# SHT4x.net
KiCad netlist of a schematic drawn in EAGLE
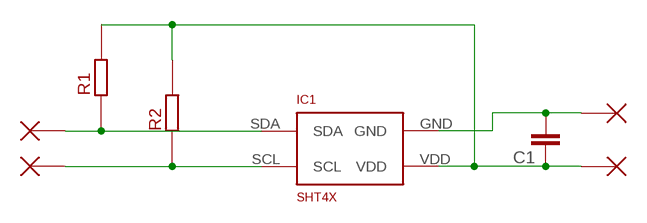
[diagram p0: schematic, sheet 1]

(export (version "E")
  (design (tool "Eeschema 10.0.6"))
  (components
    (comp (ref "C1")
      (value "SMD-C-1206")
      (footprint "eagle-import:C1206")
      (libsource (lib "eagle-import") (part "SMD-C-1206"))
    )
    (comp (ref "IC1")
      (value "SHT4X")
      (footprint "eagle-import:SHT4X")
      (libsource (lib "eagle-import") (part "SHT4X"))
    )
    (comp (ref "P1")
      (value "PIN")
      (footprint "eagle-import:PIN")
      (libsource (lib "eagle-import") (part "PIN"))
    )
    (comp (ref "P2")
      (value "PIN")
      (footprint "eagle-import:PIN")
      (libsource (lib "eagle-import") (part "PIN"))
    )
    (comp (ref "P3")
      (value "PIN")
      (footprint "eagle-import:PIN")
      (libsource (lib "eagle-import") (part "PIN"))
    )
    (comp (ref "P4")
      (value "PIN")
      (footprint "eagle-import:PIN")
      (libsource (lib "eagle-import") (part "PIN"))
    )
    (comp (ref "R1")
      (value "SMD-RR0603")
      (footprint "eagle-import:R0603")
      (libsource (lib "eagle-import") (part "SMD-RR0603"))
    )
    (comp (ref "R2")
      (value "SMD-RR0603")
      (footprint "eagle-import:R0603")
      (libsource (lib "eagle-import") (part "SMD-RR0603"))
    )
  )
  (nets
    (net (code "1") (name "Net-(C1-Pad2)") (class "Default")
      (node (ref "C1") (pin "2") (pinfunction "2_2") (pintype "passive"))
      (node (ref "IC1") (pin "GND") (pinfunction "GND_GND") (pintype "bidirectional"))
      (node (ref "P3") (pin "P$1") (pinfunction "P$1_P$1") (pintype "bidirectional"))
    )
    (net (code "2") (name "Net-(R1-P$1)") (class "Default")
      (node (ref "IC1") (pin "SDA") (pinfunction "SDA_SDA") (pintype "bidirectional"))
      (node (ref "P1") (pin "P$1") (pinfunction "P$1_P$1") (pintype "bidirectional"))
      (node (ref "R1") (pin "1") (pinfunction "P$1_1") (pintype "passive"))
    )
    (net (code "3") (name "Net-(R1-P$3)") (class "Default")
      (node (ref "C1") (pin "1") (pinfunction "1_1") (pintype "passive"))
      (node (ref "IC1") (pin "VDD") (pinfunction "VDD_VDD") (pintype "bidirectional"))
      (node (ref "P4") (pin "P$1") (pinfunction "P$1_P$1") (pintype "bidirectional"))
      (node (ref "R1") (pin "2") (pinfunction "P$3_2") (pintype "passive"))
      (node (ref "R2") (pin "2") (pinfunction "P$3_2") (pintype "passive"))
    )
    (net (code "4") (name "Net-(R2-P$1)") (class "Default")
      (node (ref "IC1") (pin "SCL") (pinfunction "SCL_SCL") (pintype "bidirectional"))
      (node (ref "P2") (pin "P$1") (pinfunction "P$1_P$1") (pintype "bidirectional"))
      (node (ref "R2") (pin "1") (pinfunction "P$1_1") (pintype "passive"))
    )
  )
)
